# Power_Supply_1V8.net
KiCad netlist of a schematic drawn in Altium Designer
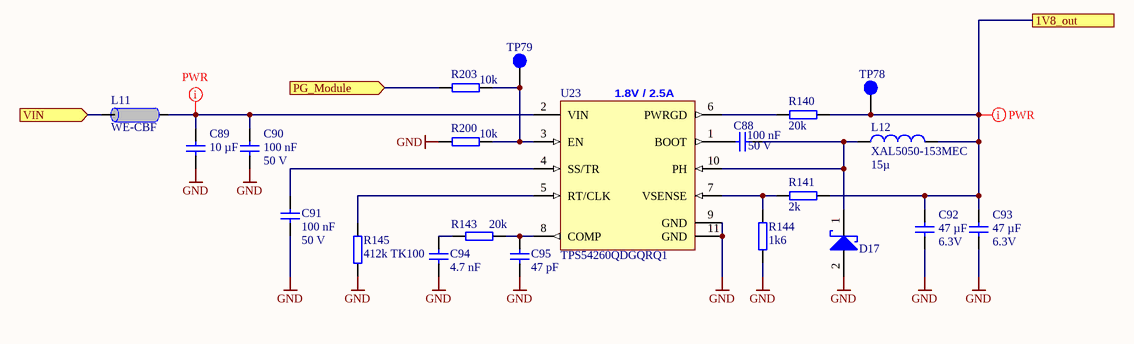
[diagram p0: Power_Supply_1V8.SchDoc]

(export (version "E")
  (design (tool "Eeschema 10.0.6"))
  (components
    (comp (ref "C88")
      (value "100 nF")
      (footprint "C_0603_TE")
      (description "Generic capacitor")
      (fields
        (field (name "TOLERANCE") "10 %")
        (field (name "VOLTAGE") "50 V")
        (field (name "MANUFACTURER PART NUMBER") "UZgen_C_0603_100nF_50V_X7R")
        (field (name "CREATED FROM") "AGeiger")
      )
      (libsource (lib "user") (part "CAP-NP"))
    )
    (comp (ref "C89")
      (value "10 µF")
      (footprint "C_1206_TE")
      (description "50V 10uF X7R ±10% 1206  Multilayer Ceramic Capacitors MLCC - SMD/SMT ROHS")
      (fields
        (field (name "TOLERANCE") "10 %")
        (field (name "MANUFACTURER PART NUMBER") "CL31B106KBHNNNE")
        (field (name "CREATED FROM") "AGeiger")
      )
      (libsource (lib "user") (part "CAP-NP"))
    )
    (comp (ref "C90")
      (value "100 nF")
      (footprint "C_0603_TE")
      (description "Generic capacitor")
      (fields
        (field (name "TOLERANCE") "10 %")
        (field (name "VOLTAGE") "50 V")
        (field (name "MANUFACTURER PART NUMBER") "UZgen_C_0603_100nF_50V_X7R")
        (field (name "CREATED FROM") "AGeiger")
      )
      (libsource (lib "user") (part "CAP-NP"))
    )
    (comp (ref "C91")
      (value "100 nF")
      (footprint "C_0603_TE")
      (description "Generic capacitor")
      (fields
        (field (name "TOLERANCE") "10 %")
        (field (name "VOLTAGE") "50 V")
        (field (name "MANUFACTURER PART NUMBER") "UZgen_C_0603_100nF_50V_X7R")
        (field (name "CREATED FROM") "AGeiger")
      )
      (libsource (lib "user") (part "CAP-NP"))
    )
    (comp (ref "C92")
      (value "47 µF")
      (footprint "C_0805_TE")
      (description "Generic capacitor")
      (fields
        (field (name "TOLERANCE") "10 %")
        (field (name "VOLTAGE") "6.3V")
        (field (name "MANUFACTURER PART NUMBER") "UZgen_C_0805_47uF_6.3V_X7R")
        (field (name "CREATED FROM") "UZgenTool")
      )
      (libsource (lib "user") (part "CAP-NP"))
    )
    (comp (ref "C93")
      (value "47 µF")
      (footprint "C_0805_TE")
      (description "Generic capacitor")
      (fields
        (field (name "TOLERANCE") "10 %")
        (field (name "VOLTAGE") "6.3V")
        (field (name "MANUFACTURER PART NUMBER") "UZgen_C_0805_47uF_6.3V_X7R")
        (field (name "CREATED FROM") "UZgenTool")
      )
      (libsource (lib "user") (part "CAP-NP"))
    )
    (comp (ref "C94")
      (value "4.7 nF")
      (footprint "C_0603_TE")
      (description "50V 4.7nF C0G ±5% 0603 Multilayer Ceramic Capacitors MLCC")
      (fields
        (field (name "TOLERANCE") "5%")
        (field (name "MANUFACTURER PART NUMBER") "GRM1885C1H472JA01D")
        (field (name "CREATED FROM") "MGeier")
      )
      (libsource (lib "user") (part "CAP-NP"))
    )
    (comp (ref "C95")
      (value "47 pF")
      (footprint "C_0603_TE")
      (description "50V 47pF C0G ±5% 0603 Multilayer Ceramic Capacitors MLCC")
      (fields
        (field (name "TOLERANCE") "5%")
        (field (name "MANUFACTURER PART NUMBER") "CL10C470JB8NNNC")
        (field (name "CREATED FROM") "MGeier")
      )
      (libsource (lib "user") (part "CAP-NP"))
    )
    (comp (ref "D17")
      (value "STPS340UY")
      (footprint "SMB")
      (description "Power Schottky Rectifier, 3 A, 40 V, 0.57 µF")
      (fields (field (name "MANUFACTURER") "STMicroelectronics") (field (name "CREATED FROM") "MGremer"))
      (libsource (lib "user") (part "STPS340-Y"))
    )
    (comp (ref "L11")
      (value "WE-CBF")
      (footprint "INDC2012X92N_V")
      (description "Ferritdurchführung SMD 0805")
      (fields (field (name "VOLTAGE") "2000mA"))
      (libsource (lib "TE") (part "Ferritperle"))
    )
    (comp (ref "L12")
      (value "XAL5050-153MEC")
      (footprint "IND_XAL5050")
      (description "Power Inductor 15µH 20% 3.9A 76.7mOhms")
      (fields (field (name "ALTIUM_VALUE") "15µ") (field (name "VOLTAGE") "3.9A 76.7mOhms"))
      (libsource (lib "TE") (part "IND"))
    )
    (comp (ref "R140")
      (value "20k")
      (footprint "R_0603_TE")
      (description "Generic resistor")
      (fields
        (field (name "TOLERANCE") "1 %")
        (field (name "MANUFACTURER PART NUMBER") "UZgen_R_0603_20k")
        (field (name "CREATED FROM") "UZgenTool")
      )
      (libsource (lib "user") (part "RES"))
    )
    (comp (ref "R141")
      (value "2k")
      (footprint "R_0603_TE")
      (description "Generic resistor")
      (fields
        (field (name "TOLERANCE") "1 %")
        (field (name "MANUFACTURER PART NUMBER") "UZgen_R_0603_2k")
        (field (name "CREATED FROM") "UZgenTool")
      )
      (libsource (lib "user") (part "RES"))
    )
    (comp (ref "R143")
      (value "20k")
      (footprint "R_0603_TE")
      (description "Generic resistor")
      (fields
        (field (name "TOLERANCE") "1 %")
        (field (name "MANUFACTURER PART NUMBER") "UZgen_R_0603_20k")
        (field (name "CREATED FROM") "UZgenTool")
      )
      (libsource (lib "user") (part "RES"))
    )
    (comp (ref "R144")
      (value "1k6")
      (footprint "R_0603_TE")
      (description "Generic resistor")
      (fields
        (field (name "TOLERANCE") "1 %")
        (field (name "MANUFACTURER PART NUMBER") "UZgen_R_0603_1k6")
        (field (name "CREATED FROM") "UZgenTool")
      )
      (libsource (lib "user") (part "RES"))
    )
    (comp (ref "R145")
      (value "412k TK100")
      (footprint "R_0603_TE")
      (description "Non generic resistor")
      (fields
        (field (name "TOLERANCE") "1 %")
        (field (name "MANUFACTURER PART NUMBER") "UZgen_R_0603_412k")
        (field (name "CREATED FROM") "UZgenTool")
      )
      (libsource (lib "user") (part "RES"))
    )
    (comp (ref "R200")
      (value "10k")
      (footprint "R_0603_TE")
      (description "Generic resistor")
      (fields
        (field (name "TOLERANCE") "1 %")
        (field (name "MANUFACTURER PART NUMBER") "UZgen_R_0603_10k")
        (field (name "CREATED FROM") "AGeiger")
      )
      (libsource (lib "user") (part "RES"))
    )
    (comp (ref "R203")
      (value "10k")
      (footprint "R_0603_TE")
      (description "Generic resistor")
      (fields
        (field (name "TOLERANCE") "1 %")
        (field (name "MANUFACTURER PART NUMBER") "UZgen_R_0603_10k")
        (field (name "CREATED FROM") "AGeiger")
      )
      (libsource (lib "user") (part "RES"))
    )
    (comp (ref "TP78") (value "Testpoint 1mm") (footprint "TP_1mm") (libsource (lib "TE") (part "TP")))
    (comp (ref "TP79") (value "Testpoint 1mm") (footprint "TP_1mm") (libsource (lib "TE") (part "TP")))
    (comp (ref "U23")
      (value "TPS54260QDGQRQ1")
      (footprint "TSSOP50P490X110-11N-TI-DGQ")
      (description "Switching Voltage Regulators 3.5-42Vin,2.5A,2.5 MHz Step-Down Cnvrtr")
      (fields
        (field (name "MANUFACTURER") "Texas Instruments")
        (field (name "LCSC PART NUMBER") "C181278")
        (field (name "CREATED FROM") "FRosner")
      )
      (libsource (lib "user") (part "TPS54260"))
    )
  )
  (nets
    (net (code "1") (name "/1V8_out") (class "Default")
      (node (ref "C92") (pin "2") (pinfunction "2_2") (pintype "passive"))
      (node (ref "C93") (pin "2") (pinfunction "2_2") (pintype "passive"))
      (node (ref "L12") (pin "2") (pinfunction "2_2") (pintype "passive"))
      (node (ref "R140") (pin "1") (pinfunction "1_1") (pintype "passive"))
      (node (ref "R141") (pin "1") (pinfunction "1_1") (pintype "passive"))
      (node (ref "TP78") (pin "1") (pintype "passive"))
    )
    (net (code "2") (name "/PG_Module") (class "Default")
      (node (ref "R203") (pin "1") (pinfunction "1_1") (pintype "passive"))
    )
    (net (code "3") (name "/VIN") (class "Default")
      (node (ref "L11") (pin "2") (pinfunction "2_2") (pintype "passive"))
    )
    (net (code "4") (name "GND") (class "Default")
      (node (ref "C89") (pin "2") (pinfunction "2_2") (pintype "passive"))
      (node (ref "C90") (pin "1") (pinfunction "1_1") (pintype "passive"))
      (node (ref "C91") (pin "1") (pinfunction "1_1") (pintype "passive"))
      (node (ref "C92") (pin "1") (pinfunction "1_1") (pintype "passive"))
      (node (ref "C93") (pin "1") (pinfunction "1_1") (pintype "passive"))
      (node (ref "C94") (pin "2") (pinfunction "2_2") (pintype "passive"))
      (node (ref "C95") (pin "2") (pinfunction "2_2") (pintype "passive"))
      (node (ref "D17") (pin "2") (pinfunction "A_2") (pintype "passive"))
      (node (ref "R144") (pin "2") (pinfunction "2_2") (pintype "passive"))
      (node (ref "R145") (pin "2") (pinfunction "2_2") (pintype "passive"))
      (node (ref "R200") (pin "1") (pinfunction "1_1") (pintype "passive"))
      (node (ref "U23") (pin "11") (pinfunction "GND_11") (pintype "power_in"))
      (node (ref "U23") (pin "9") (pinfunction "GND_9") (pintype "power_in"))
    )
    (net (code "5") (name "Net-(C94-Pad1)") (class "Default")
      (node (ref "C94") (pin "1") (pinfunction "1_1") (pintype "passive"))
      (node (ref "R143") (pin "2") (pinfunction "2_2") (pintype "passive"))
    )
    (net (code "6") (name "Net-(D17-K)") (class "Default")
      (node (ref "C88") (pin "1") (pinfunction "1_1") (pintype "passive"))
      (node (ref "D17") (pin "1") (pinfunction "K_1") (pintype "passive"))
      (node (ref "L12") (pin "1") (pinfunction "1_1") (pintype "passive"))
      (node (ref "U23") (pin "10") (pinfunction "PH_10") (pintype "input"))
    )
    (net (code "7") (name "Net-(U23-BOOT)") (class "Default")
      (node (ref "C88") (pin "2") (pinfunction "2_2") (pintype "passive"))
      (node (ref "U23") (pin "1") (pinfunction "BOOT_1") (pintype "output"))
    )
    (net (code "8") (name "Net-(U23-COMP)") (class "Default")
      (node (ref "C95") (pin "1") (pinfunction "1_1") (pintype "passive"))
      (node (ref "R143") (pin "1") (pinfunction "1_1") (pintype "passive"))
      (node (ref "U23") (pin "8") (pinfunction "COMP_8") (pintype "output"))
    )
    (net (code "9") (name "Net-(U23-EN)") (class "Default")
      (node (ref "R200") (pin "2") (pinfunction "2_2") (pintype "passive"))
      (node (ref "R203") (pin "2") (pinfunction "2_2") (pintype "passive"))
      (node (ref "TP79") (pin "1") (pintype "passive"))
      (node (ref "U23") (pin "3") (pinfunction "EN_3") (pintype "input"))
    )
    (net (code "10") (name "Net-(U23-PWRGD)") (class "Default")
      (node (ref "R140") (pin "2") (pinfunction "2_2") (pintype "passive"))
      (node (ref "U23") (pin "6") (pinfunction "PWRGD_6") (pintype "output"))
    )
    (net (code "11") (name "Net-(U23-RT{slash}CLK)") (class "Default")
      (node (ref "R145") (pin "1") (pinfunction "1_1") (pintype "passive"))
      (node (ref "U23") (pin "5") (pinfunction "RT/CLK_5") (pintype "input"))
    )
    (net (code "12") (name "Net-(U23-SS{slash}TR)") (class "Default")
      (node (ref "C91") (pin "2") (pinfunction "2_2") (pintype "passive"))
      (node (ref "U23") (pin "4") (pinfunction "SS/TR_4") (pintype "input"))
    )
    (net (code "13") (name "Net-(U23-VIN)") (class "Default")
      (node (ref "C89") (pin "1") (pinfunction "1_1") (pintype "passive"))
      (node (ref "C90") (pin "2") (pinfunction "2_2") (pintype "passive"))
      (node (ref "L11") (pin "1") (pinfunction "1_1") (pintype "passive"))
      (node (ref "U23") (pin "2") (pinfunction "VIN_2") (pintype "power_in"))
    )
    (net (code "14") (name "Net-(U23-VSENSE)") (class "Default")
      (node (ref "R141") (pin "2") (pinfunction "2_2") (pintype "passive"))
      (node (ref "R144") (pin "1") (pinfunction "1_1") (pintype "passive"))
      (node (ref "U23") (pin "7") (pinfunction "VSENSE_7") (pintype "input"))
    )
  )
)
